# HLK-M20_8266-SUIT-V2_1.net
KiCad netlist of a schematic drawn in Altium Designer
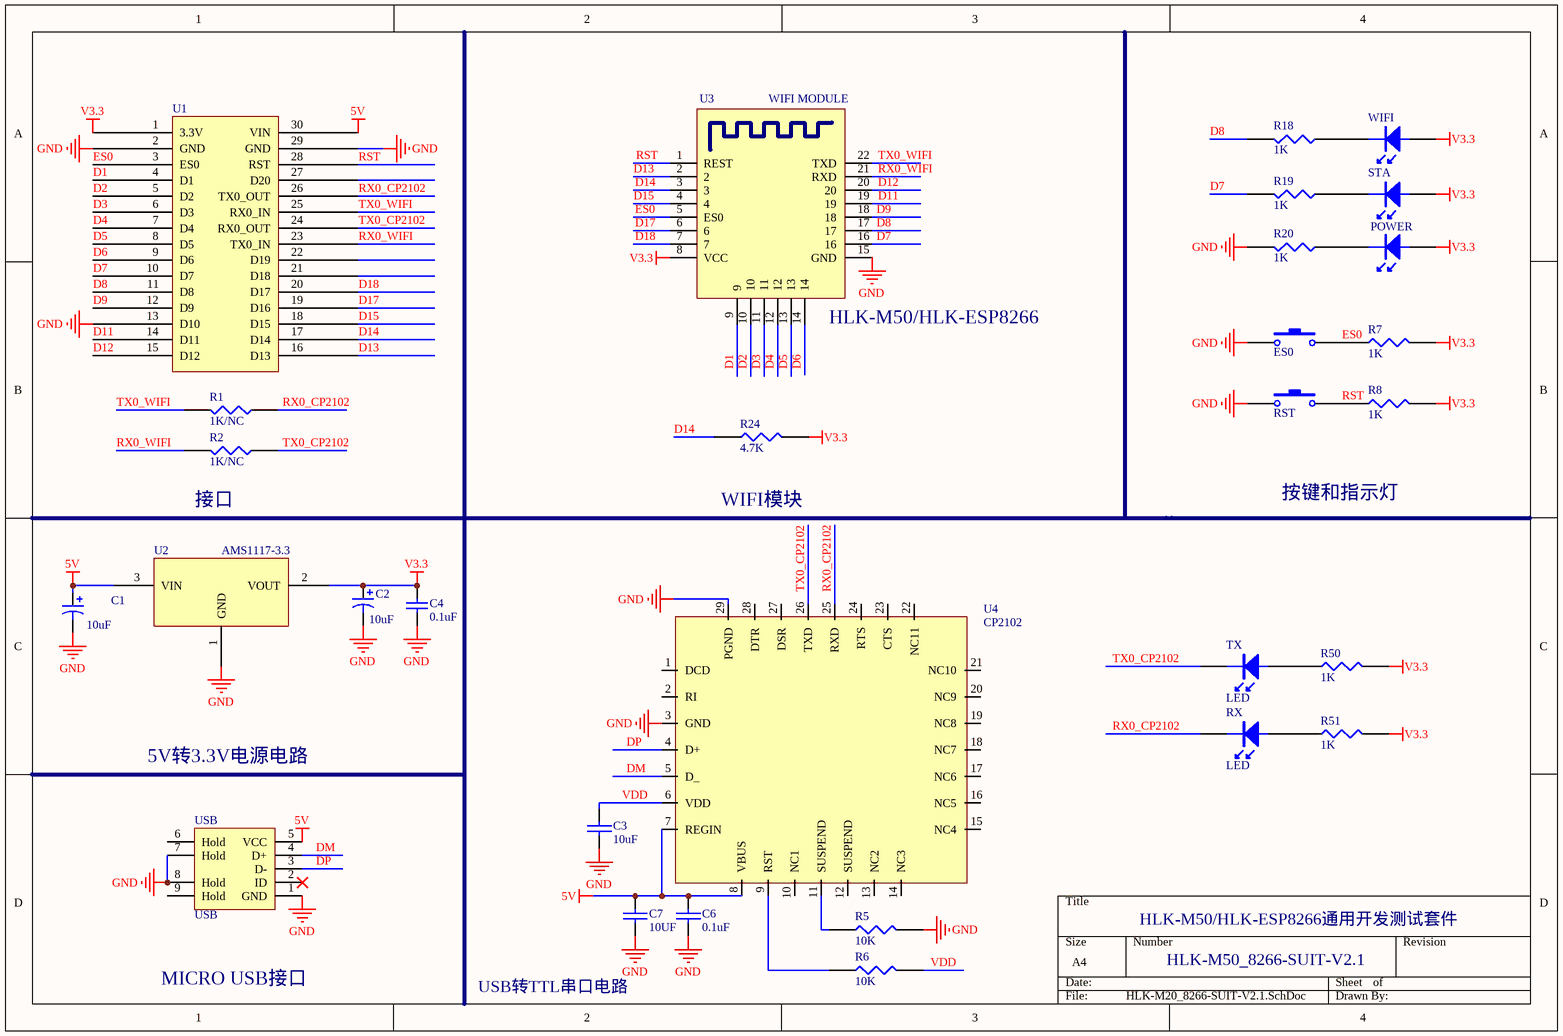
[diagram p0: HLK-M20_8266-SUIT-V2.1.SchDoc]

(export (version "E")
  (design (tool "Eeschema 10.0.6"))
  (components
    (comp (ref "C1")
      (value "10uF")
      (footprint "0805S")
      (description "Polarized Capacitor (Axial)")
      (fields (field (name "PUBLISHER") "*"))
      (libsource (lib "*") (part "Cap Pol2"))
    )
    (comp (ref "C2")
      (value "10uF")
      (footprint "0805S")
      (description "Polarized Capacitor (Axial)")
      (fields (field (name "PUBLISHER") "*"))
      (libsource (lib "*") (part "Cap Pol2"))
    )
    (comp (ref "C3")
      (value "10uF")
      (footprint "0603L")
      (description "Capacitor")
      (libsource (lib "Jerry") (part "CAP"))
    )
    (comp (ref "C4")
      (value "0.1uF")
      (footprint "0603L")
      (description "Capacitor")
      (fields (field (name "PUBLISHER") "*"))
      (libsource (lib "*") (part "Cap"))
    )
    (comp (ref "C6")
      (value "0.1uF")
      (footprint "0603L")
      (description "Capacitor")
      (libsource (lib "Jerry") (part "CAP"))
    )
    (comp (ref "C7")
      (value "10UF")
      (footprint "0603L")
      (description "Capacitor")
      (libsource (lib "Jerry") (part "CAP"))
    )
    (comp (ref "ES0")
      (value "SW-PB")
      (footprint "小按键")
      (description "Switch")
      (fields (field (name "PUBLISHER") "Altium Limited"))
      (libsource (lib "Miscellaneous Devices") (part "SW-PB"))
    )
    (comp (ref "POWER")
      (value "LED")
      (footprint "0603LED")
      (libsource (lib "Miscellaneous Devices") (part "LED"))
    )
    (comp (ref "R1") (value "1K/NC") (footprint "0603L") (libsource (lib "*") (part "RES1")))
    (comp (ref "R2") (value "1K/NC") (footprint "0603L") (libsource (lib "*") (part "RES1")))
    (comp (ref "R5") (value "10K") (footprint "0603L") (libsource (lib "*") (part "RES1")))
    (comp (ref "R6") (value "10K") (footprint "0603L") (libsource (lib "*") (part "RES1")))
    (comp (ref "R7") (value "1K") (footprint "0603L") (libsource (lib "*") (part "RES1")))
    (comp (ref "R8") (value "1K") (footprint "0603L") (libsource (lib "*") (part "RES1")))
    (comp (ref "R18") (value "1K") (footprint "0603L") (libsource (lib "*") (part "RES1")))
    (comp (ref "R19") (value "1K") (footprint "0603L") (libsource (lib "*") (part "RES1")))
    (comp (ref "R20") (value "1K") (footprint "0603L") (libsource (lib "*") (part "RES1")))
    (comp (ref "R24") (value "4.7K") (footprint "0603L") (libsource (lib "*") (part "RES1")))
    (comp (ref "R50") (value "1K") (footprint "0603L") (libsource (lib "*") (part "RES1")))
    (comp (ref "R51") (value "1K") (footprint "0603L") (libsource (lib "*") (part "RES1")))
    (comp (ref "RST")
      (value "SW-PB")
      (footprint "小按键")
      (description "Switch")
      (fields (field (name "PUBLISHER") "Altium Limited"))
      (libsource (lib "Miscellaneous Devices") (part "SW-PB"))
    )
    (comp (ref "RX") (value "LED") (footprint "0603LED") (libsource (lib "*") (part "LED")))
    (comp (ref "STA")
      (value "LED3")
      (footprint "0603LED")
      (libsource (lib "Miscellaneous Devices") (part "LED"))
    )
    (comp (ref "TX") (value "LED") (footprint "0603LED") (libsource (lib "*") (part "LED")))
    (comp (ref "U1") (value "~") (footprint "转接板") (libsource (lib "Schlib1") (part "转接板")))
    (comp (ref "U2")
      (value "AMS1117-3.3")
      (footprint "AMS1117")
      (libsource (lib "AMS1117") (part "AMS1117-3.3"))
    )
    (comp (ref "U3") (value "WIFI MODULE") (footprint "MOD1") (libsource (lib "mod") (part "MOD1")))
    (comp (ref "U4") (value "CP2102") (footprint "cp2102") (libsource (lib "Schlib1") (part "Component_1")))
    (comp (ref "USB") (value "USB") (footprint "usb") (libsource (lib "*") (part "USB-B")))
    (comp (ref "WIFI")
      (value "LED2")
      (footprint "0603LED")
      (libsource (lib "Miscellaneous Devices") (part "LED"))
    )
  )
  (nets
    (net (code "1") (name "/D1") (class "Default")
      (node (ref "U1") (pin "4") (pinfunction "D1_4") (pintype "passive"))
      (node (ref "U3") (pin "9") (pinfunction "9_9") (pintype "passive"))
    )
    (net (code "2") (name "/D2") (class "Default")
      (node (ref "U1") (pin "5") (pinfunction "D2_5") (pintype "passive"))
      (node (ref "U3") (pin "10") (pinfunction "10_10") (pintype "passive"))
    )
    (net (code "3") (name "/D3") (class "Default")
      (node (ref "U1") (pin "6") (pinfunction "D3_6") (pintype "passive"))
      (node (ref "U3") (pin "11") (pinfunction "11_11") (pintype "passive"))
    )
    (net (code "4") (name "/D4") (class "Default")
      (node (ref "U1") (pin "7") (pinfunction "D4_7") (pintype "passive"))
      (node (ref "U3") (pin "12") (pinfunction "12_12") (pintype "passive"))
    )
    (net (code "5") (name "/D5") (class "Default")
      (node (ref "U1") (pin "8") (pinfunction "D5_8") (pintype "passive"))
      (node (ref "U3") (pin "13") (pinfunction "13_13") (pintype "passive"))
    )
    (net (code "6") (name "/D6") (class "Default")
      (node (ref "U1") (pin "9") (pinfunction "D6_9") (pintype "passive"))
      (node (ref "U3") (pin "14") (pinfunction "14_14") (pintype "passive"))
    )
    (net (code "7") (name "/D7") (class "Default")
      (node (ref "R19") (pin "2") (pinfunction "2_2") (pintype "passive"))
      (node (ref "U1") (pin "10") (pinfunction "D7_10") (pintype "passive"))
      (node (ref "U3") (pin "16") (pinfunction "16_16") (pintype "passive"))
    )
    (net (code "8") (name "/D8") (class "Default")
      (node (ref "R18") (pin "2") (pinfunction "2_2") (pintype "passive"))
      (node (ref "U1") (pin "11") (pinfunction "D8_11") (pintype "passive"))
      (node (ref "U3") (pin "17") (pinfunction "17_17") (pintype "passive"))
    )
    (net (code "9") (name "/D9") (class "Default")
      (node (ref "U1") (pin "12") (pinfunction "D9_12") (pintype "passive"))
      (node (ref "U3") (pin "18") (pinfunction "18_18") (pintype "passive"))
    )
    (net (code "10") (name "/D11") (class "Default")
      (node (ref "U1") (pin "14") (pinfunction "D11_14") (pintype "passive"))
      (node (ref "U3") (pin "19") (pinfunction "19_19") (pintype "passive"))
    )
    (net (code "11") (name "/D12") (class "Default")
      (node (ref "U1") (pin "15") (pinfunction "D12_15") (pintype "passive"))
      (node (ref "U3") (pin "20") (pinfunction "20_20") (pintype "passive"))
    )
    (net (code "12") (name "/D13") (class "Default")
      (node (ref "U1") (pin "16") (pinfunction "D13_16") (pintype "passive"))
      (node (ref "U3") (pin "2") (pinfunction "2_2") (pintype "passive"))
    )
    (net (code "13") (name "/D14") (class "Default")
      (node (ref "R24") (pin "1") (pinfunction "1_1") (pintype "passive"))
      (node (ref "U1") (pin "17") (pinfunction "D14_17") (pintype "passive"))
      (node (ref "U3") (pin "3") (pinfunction "3_3") (pintype "passive"))
    )
    (net (code "14") (name "/D15") (class "Default")
      (node (ref "U1") (pin "18") (pinfunction "D15_18") (pintype "passive"))
      (node (ref "U3") (pin "4") (pinfunction "4_4") (pintype "passive"))
    )
    (net (code "15") (name "/D17") (class "Default")
      (node (ref "U1") (pin "19") (pinfunction "D16_19") (pintype "passive"))
      (node (ref "U3") (pin "6") (pinfunction "6_6") (pintype "passive"))
    )
    (net (code "16") (name "/D18") (class "Default")
      (node (ref "U1") (pin "20") (pinfunction "D17_20") (pintype "passive"))
      (node (ref "U3") (pin "7") (pinfunction "7_7") (pintype "passive"))
    )
    (net (code "17") (name "/DM") (class "Default")
      (node (ref "U4") (pin "5") (pinfunction "D__5") (pintype "passive"))
      (node (ref "USB") (pin "4") (pinfunction "D+_4") (pintype "passive"))
    )
    (net (code "18") (name "/DP") (class "Default")
      (node (ref "U4") (pin "4") (pinfunction "D+_4") (pintype "passive"))
      (node (ref "USB") (pin "3") (pinfunction "D-_3") (pintype "passive"))
    )
    (net (code "19") (name "/ES0") (class "Default")
      (node (ref "ES0") (pin "1") (pinfunction "1_1") (pintype "passive"))
      (node (ref "R7") (pin "1") (pinfunction "1_1") (pintype "passive"))
      (node (ref "U1") (pin "3") (pinfunction "ES0_3") (pintype "passive"))
      (node (ref "U3") (pin "5") (pinfunction "ES0_5") (pintype "passive"))
    )
    (net (code "20") (name "/RST") (class "Default")
      (node (ref "R8") (pin "1") (pinfunction "1_1") (pintype "passive"))
      (node (ref "RST") (pin "1") (pinfunction "1_1") (pintype "passive"))
      (node (ref "U1") (pin "28") (pinfunction "RST_28") (pintype "passive"))
      (node (ref "U3") (pin "1") (pinfunction "REST_1") (pintype "passive"))
    )
    (net (code "21") (name "/RX0_CP2102") (class "Default")
      (node (ref "R1") (pin "1") (pinfunction "1_1") (pintype "passive"))
      (node (ref "RX") (pin "2") (pinfunction "2_2") (pintype "passive"))
      (node (ref "U1") (pin "26") (pinfunction "TX0_OUT_26") (pintype "passive"))
      (node (ref "U4") (pin "25") (pinfunction "RXD_25") (pintype "passive"))
    )
    (net (code "22") (name "/RX0_WIFI") (class "Default")
      (node (ref "R2") (pin "2") (pinfunction "2_2") (pintype "passive"))
      (node (ref "U1") (pin "23") (pinfunction "TX0_IN_23") (pintype "passive"))
      (node (ref "U3") (pin "21") (pinfunction "RXD_21") (pintype "passive"))
    )
    (net (code "23") (name "/TX0_CP2102") (class "Default")
      (node (ref "R2") (pin "1") (pinfunction "1_1") (pintype "passive"))
      (node (ref "TX") (pin "2") (pinfunction "2_2") (pintype "passive"))
      (node (ref "U1") (pin "24") (pinfunction "RX0_OUT_24") (pintype "passive"))
      (node (ref "U4") (pin "26") (pinfunction "TXD_26") (pintype "passive"))
    )
    (net (code "24") (name "/TX0_WIFI") (class "Default")
      (node (ref "R1") (pin "2") (pinfunction "2_2") (pintype "passive"))
      (node (ref "U1") (pin "25") (pinfunction "RX0_IN_25") (pintype "passive"))
      (node (ref "U3") (pin "22") (pinfunction "TXD_22") (pintype "passive"))
    )
    (net (code "25") (name "/VDD") (class "Default")
      (node (ref "C3") (pin "2") (pinfunction "2_2") (pintype "passive"))
      (node (ref "R6") (pin "2") (pinfunction "2_2") (pintype "passive"))
      (node (ref "U4") (pin "6") (pinfunction "VDD_6") (pintype "passive"))
    )
    (net (code "26") (name "5V") (class "Default")
      (node (ref "C1") (pin "1") (pinfunction "1_1") (pintype "passive"))
      (node (ref "C6") (pin "2") (pinfunction "2_2") (pintype "passive"))
      (node (ref "C7") (pin "2") (pinfunction "2_2") (pintype "passive"))
      (node (ref "U1") (pin "30") (pinfunction "VIN_30") (pintype "passive"))
      (node (ref "U2") (pin "3") (pinfunction "VIN_3") (pintype "passive"))
      (node (ref "U4") (pin "7") (pinfunction "REGIN_7") (pintype "passive"))
      (node (ref "U4") (pin "8") (pinfunction "VBUS_8") (pintype "passive"))
      (node (ref "USB") (pin "5") (pinfunction "VCC_5") (pintype "passive"))
    )
    (net (code "27") (name "GND") (class "Default")
      (node (ref "C1") (pin "2") (pinfunction "2_2") (pintype "passive"))
      (node (ref "C2") (pin "2") (pinfunction "2_2") (pintype "passive"))
      (node (ref "C3") (pin "1") (pinfunction "1_1") (pintype "passive"))
      (node (ref "C4") (pin "1") (pinfunction "1_1") (pintype "passive"))
      (node (ref "C6") (pin "1") (pinfunction "1_1") (pintype "passive"))
      (node (ref "C7") (pin "1") (pinfunction "1_1") (pintype "passive"))
      (node (ref "ES0") (pin "2") (pinfunction "2_2") (pintype "passive"))
      (node (ref "R20") (pin "2") (pinfunction "2_2") (pintype "passive"))
      (node (ref "R5") (pin "2") (pinfunction "2_2") (pintype "passive"))
      (node (ref "RST") (pin "2") (pinfunction "2_2") (pintype "passive"))
      (node (ref "U1") (pin "13") (pinfunction "D10_13") (pintype "passive"))
      (node (ref "U1") (pin "2") (pinfunction "GND_2") (pintype "passive"))
      (node (ref "U1") (pin "29") (pinfunction "GND_29") (pintype "passive"))
      (node (ref "U2") (pin "1") (pinfunction "GND_1") (pintype "passive"))
      (node (ref "U3") (pin "15") (pinfunction "GND_15") (pintype "passive"))
      (node (ref "U4") (pin "29") (pinfunction "PGND_29") (pintype "passive"))
      (node (ref "U4") (pin "3") (pinfunction "GND_3") (pintype "passive"))
      (node (ref "USB") (pin "1") (pinfunction "GND_1") (pintype "passive"))
      (node (ref "USB") (pin "7") (pinfunction "Hold_7") (pintype "passive"))
      (node (ref "USB") (pin "8") (pinfunction "Hold_8") (pintype "passive"))
    )
    (net (code "28") (name "Net-(POWER-Pad2)") (class "Default")
      (node (ref "POWER") (pin "2") (pinfunction "2_2") (pintype "passive"))
      (node (ref "R20") (pin "1") (pinfunction "1_1") (pintype "passive"))
    )
    (net (code "29") (name "Net-(R5-Pad1)") (class "Default")
      (node (ref "R5") (pin "1") (pinfunction "1_1") (pintype "passive"))
      (node (ref "U4") (pin "11") (pinfunction "SUSPEND_11") (pintype "passive"))
    )
    (net (code "30") (name "Net-(R18-Pad1)") (class "Default")
      (node (ref "R18") (pin "1") (pinfunction "1_1") (pintype "passive"))
      (node (ref "WIFI") (pin "2") (pinfunction "2_2") (pintype "passive"))
    )
    (net (code "31") (name "Net-(R19-Pad1)") (class "Default")
      (node (ref "R19") (pin "1") (pinfunction "1_1") (pintype "passive"))
      (node (ref "STA") (pin "2") (pinfunction "2_2") (pintype "passive"))
    )
    (net (code "32") (name "Net-(R50-Pad1)") (class "Default")
      (node (ref "R50") (pin "1") (pinfunction "1_1") (pintype "passive"))
      (node (ref "TX") (pin "1") (pinfunction "1_1") (pintype "passive"))
    )
    (net (code "33") (name "Net-(R51-Pad1)") (class "Default")
      (node (ref "R51") (pin "1") (pinfunction "1_1") (pintype "passive"))
      (node (ref "RX") (pin "1") (pinfunction "1_1") (pintype "passive"))
    )
    (net (code "34") (name "Net-(U4-RST)") (class "Default")
      (node (ref "R6") (pin "1") (pinfunction "1_1") (pintype "passive"))
      (node (ref "U4") (pin "9") (pinfunction "RST_9") (pintype "passive"))
    )
    (net (code "35") (name "V3.3") (class "Default")
      (node (ref "C2") (pin "1") (pinfunction "1_1") (pintype "passive"))
      (node (ref "C4") (pin "2") (pinfunction "2_2") (pintype "passive"))
      (node (ref "POWER") (pin "1") (pinfunction "1_1") (pintype "passive"))
      (node (ref "R24") (pin "2") (pinfunction "2_2") (pintype "passive"))
      (node (ref "R50") (pin "2") (pinfunction "2_2") (pintype "passive"))
      (node (ref "R51") (pin "2") (pinfunction "2_2") (pintype "passive"))
      (node (ref "R7") (pin "2") (pinfunction "2_2") (pintype "passive"))
      (node (ref "R8") (pin "2") (pinfunction "2_2") (pintype "passive"))
      (node (ref "STA") (pin "1") (pinfunction "1_1") (pintype "passive"))
      (node (ref "U1") (pin "1") (pinfunction "3.3V_1") (pintype "passive"))
      (node (ref "U2") (pin "2") (pinfunction "VOUT_2") (pintype "passive"))
      (node (ref "U3") (pin "8") (pinfunction "VCC_8") (pintype "passive"))
      (node (ref "WIFI") (pin "1") (pinfunction "1_1") (pintype "passive"))
    )
    (net (code "36") (name "unconnected-(U1-D18-Pad21)") (class "Default")
      (node (ref "U1") (pin "21") (pinfunction "D18_21") (pintype "passive"))
    )
    (net (code "37") (name "unconnected-(U1-D19-Pad22)") (class "Default")
      (node (ref "U1") (pin "22") (pinfunction "D19_22") (pintype "passive"))
    )
    (net (code "38") (name "unconnected-(U1-D20-Pad27)") (class "Default")
      (node (ref "U1") (pin "27") (pinfunction "D20_27") (pintype "passive"))
    )
    (net (code "39") (name "unconnected-(U4-CTS-Pad23)") (class "Default")
      (node (ref "U4") (pin "23") (pinfunction "CTS_23") (pintype "passive"))
    )
    (net (code "40") (name "unconnected-(U4-DCD-Pad1)") (class "Default")
      (node (ref "U4") (pin "1") (pinfunction "DCD_1") (pintype "passive"))
    )
    (net (code "41") (name "unconnected-(U4-DSR-Pad27)") (class "Default")
      (node (ref "U4") (pin "27") (pinfunction "DSR_27") (pintype "passive"))
    )
    (net (code "42") (name "unconnected-(U4-DTR-Pad28)") (class "Default")
      (node (ref "U4") (pin "28") (pinfunction "DTR_28") (pintype "passive"))
    )
    (net (code "43") (name "unconnected-(U4-NC1-Pad10)") (class "Default")
      (node (ref "U4") (pin "10") (pinfunction "NC1_10") (pintype "passive"))
    )
    (net (code "44") (name "unconnected-(U4-NC2-Pad13)") (class "Default")
      (node (ref "U4") (pin "13") (pinfunction "NC2_13") (pintype "passive"))
    )
    (net (code "45") (name "unconnected-(U4-NC3-Pad14)") (class "Default")
      (node (ref "U4") (pin "14") (pinfunction "NC3_14") (pintype "passive"))
    )
    (net (code "46") (name "unconnected-(U4-NC4-Pad15)") (class "Default")
      (node (ref "U4") (pin "15") (pinfunction "NC4_15") (pintype "passive"))
    )
    (net (code "47") (name "unconnected-(U4-NC5-Pad16)") (class "Default")
      (node (ref "U4") (pin "16") (pinfunction "NC5_16") (pintype "passive"))
    )
    (net (code "48") (name "unconnected-(U4-NC6-Pad17)") (class "Default")
      (node (ref "U4") (pin "17") (pinfunction "NC6_17") (pintype "passive"))
    )
    (net (code "49") (name "unconnected-(U4-NC7-Pad18)") (class "Default")
      (node (ref "U4") (pin "18") (pinfunction "NC7_18") (pintype "passive"))
    )
    (net (code "50") (name "unconnected-(U4-NC8-Pad19)") (class "Default")
      (node (ref "U4") (pin "19") (pinfunction "NC8_19") (pintype "passive"))
    )
    (net (code "51") (name "unconnected-(U4-NC9-Pad20)") (class "Default")
      (node (ref "U4") (pin "20") (pinfunction "NC9_20") (pintype "passive"))
    )
    (net (code "52") (name "unconnected-(U4-NC10-Pad21)") (class "Default")
      (node (ref "U4") (pin "21") (pinfunction "NC10_21") (pintype "passive"))
    )
    (net (code "53") (name "unconnected-(U4-NC11-Pad22)") (class "Default")
      (node (ref "U4") (pin "22") (pinfunction "NC11_22") (pintype "passive"))
    )
    (net (code "54") (name "unconnected-(U4-RI-Pad2)") (class "Default")
      (node (ref "U4") (pin "2") (pinfunction "RI_2") (pintype "passive"))
    )
    (net (code "55") (name "unconnected-(U4-RTS-Pad24)") (class "Default")
      (node (ref "U4") (pin "24") (pinfunction "RTS_24") (pintype "passive"))
    )
    (net (code "56") (name "unconnected-(U4-SUSPEND-Pad12)") (class "Default")
      (node (ref "U4") (pin "12") (pinfunction "SUSPEND_12") (pintype "passive"))
    )
    (net (code "57") (name "unconnected-(USB-Hold-Pad6)") (class "Default")
      (node (ref "USB") (pin "6") (pinfunction "Hold_6") (pintype "passive"))
    )
    (net (code "58") (name "unconnected-(USB-Hold-Pad9)") (class "Default")
      (node (ref "USB") (pin "9") (pinfunction "Hold_9") (pintype "passive"))
    )
    (net (code "59") (name "unconnected-(USB-ID-Pad2)") (class "Default")
      (node (ref "USB") (pin "2") (pinfunction "ID_2") (pintype "passive+no_connect"))
    )
  )
)
